# Schema.net
KiCad netlist of a schematic drawn in Altium Designer
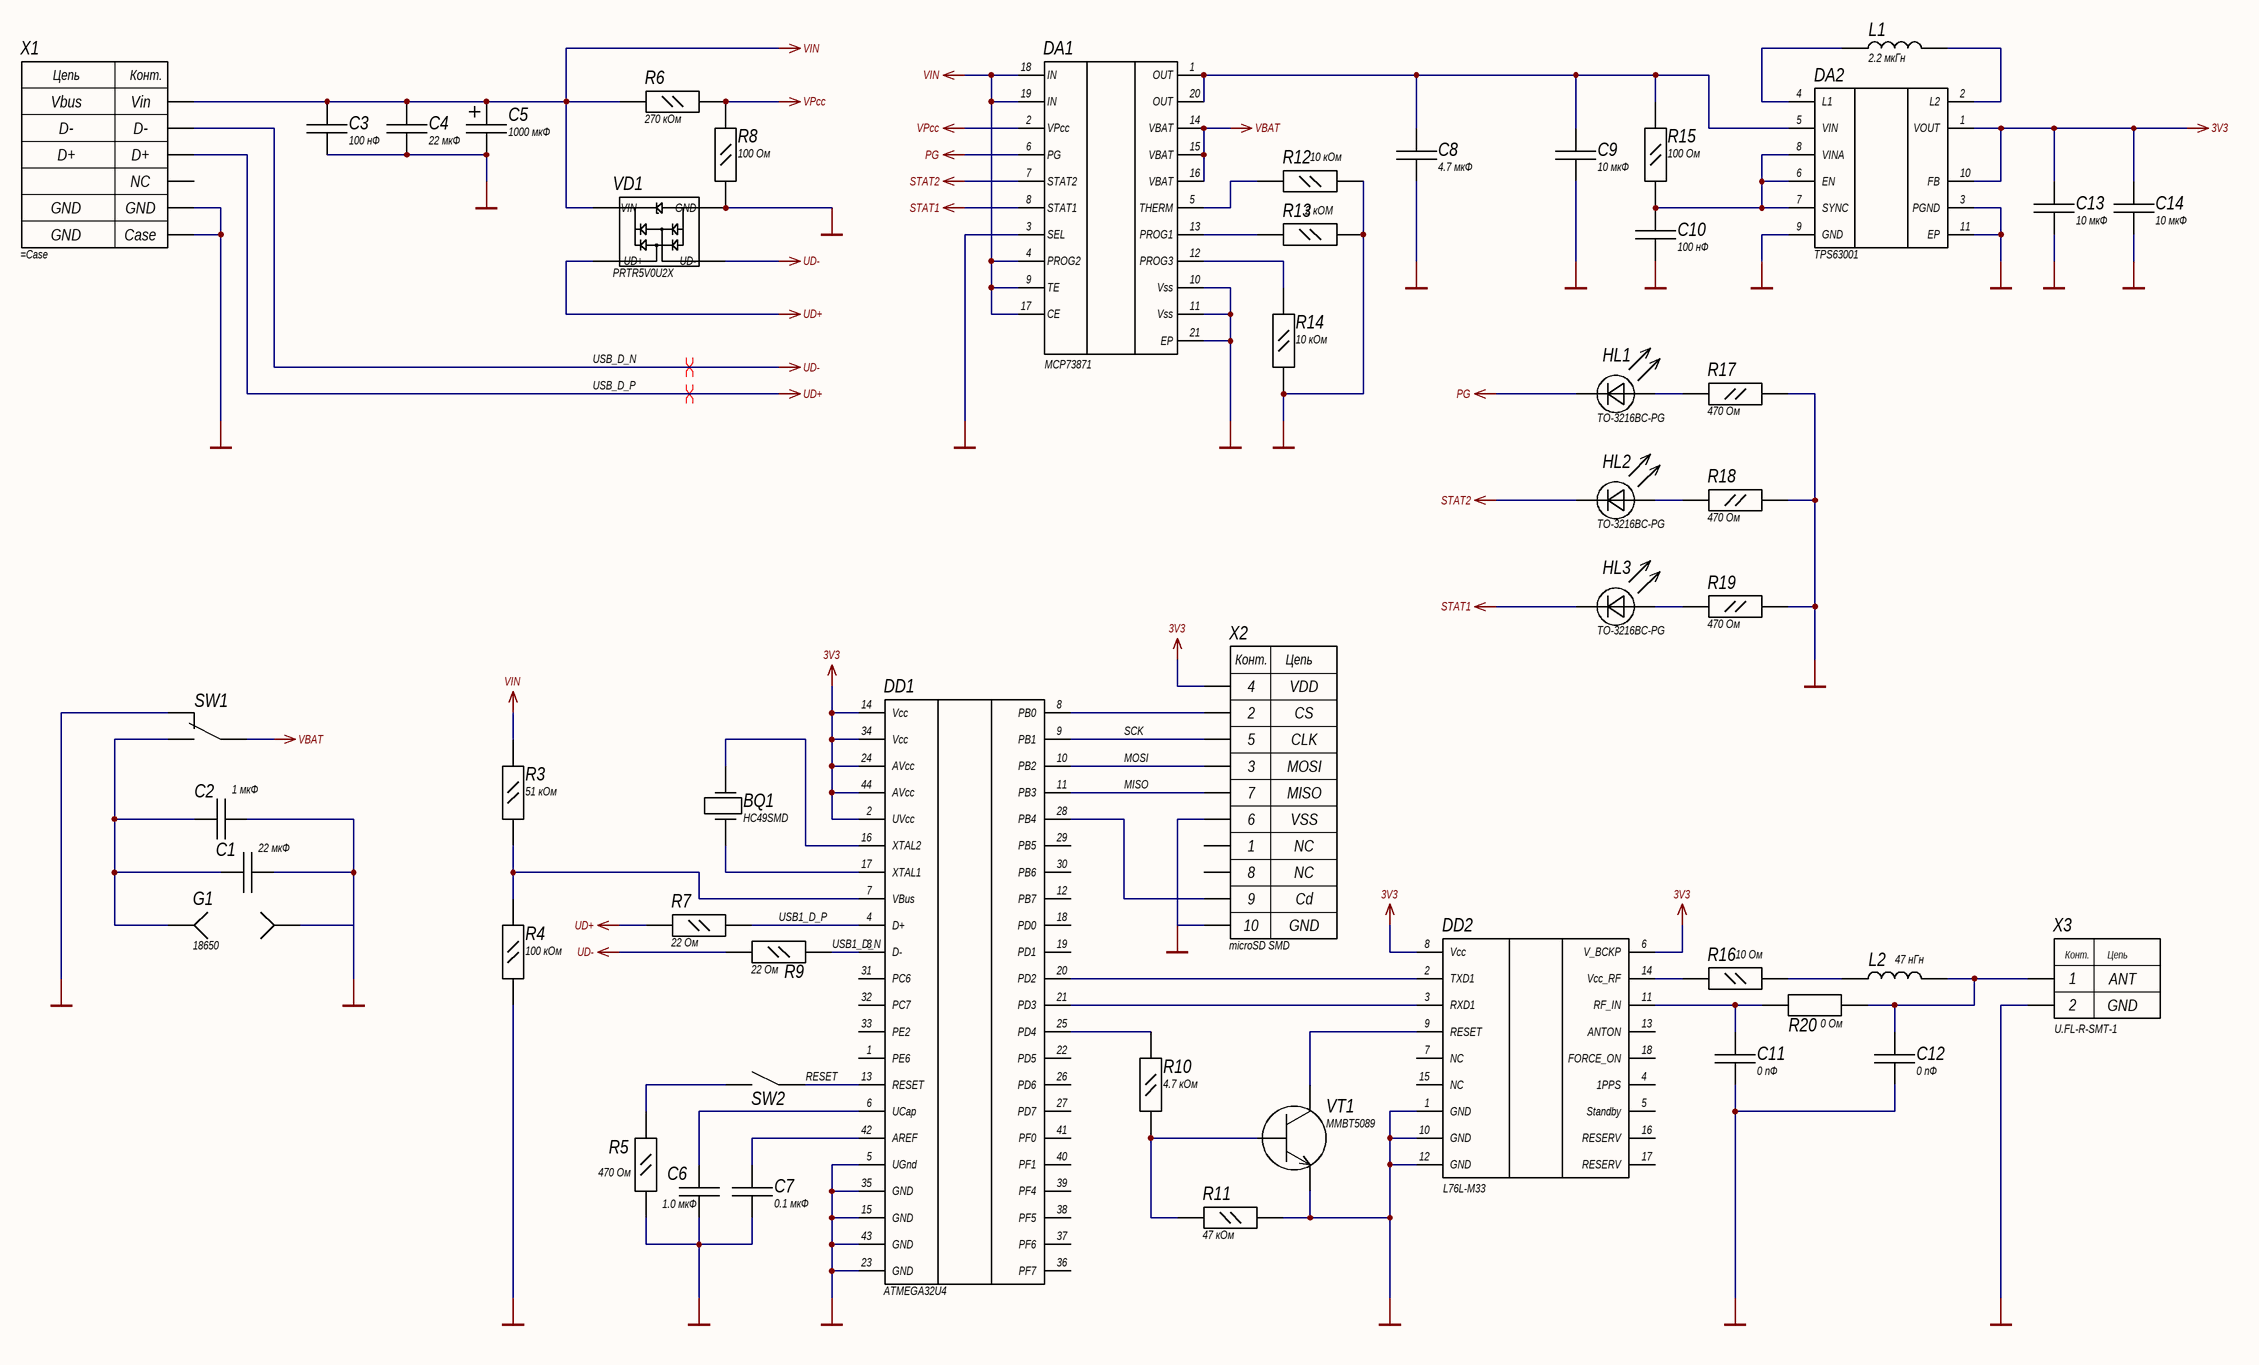
[diagram p0: Schema.SchDoc]

(export (version "E")
  (design (tool "Eeschema 10.0.6"))
  (components
    (comp (ref "BQ1")
      (value "HC49SMD")
      (footprint "HC49SMD")
      (description "Кварцевый резонатор , монтаж SMD")
      (fields (field (name "TOLERANCE") "20 ppm"))
      (libsource (lib "MarginLib") (part "Quartz"))
    )
    (comp (ref "C1")
      (value "22 мкФ")
      (footprint "CC0805")
      (description "безвыводные керамические неполярные конденсаторы общего применения")
      (fields (field (name "PART NUMBER") "GRM21BR61E226ME44L") (field (name "TOLERANCE") "20%"))
      (libsource (lib "MarginLib") (part "Capasitor"))
    )
    (comp (ref "C2")
      (value "1 мкФ")
      (footprint "CC0805")
      (description "безвыводные керамические неполярные конденсаторы общего применения")
      (fields (field (name "PART NUMBER") "GRM21BR71H105KA12L") (field (name "TOLERANCE") "10%"))
      (libsource (lib "MarginLib") (part "Capasitor"))
    )
    (comp (ref "C3")
      (value "100 нФ")
      (footprint "CC0805")
      (description "безвыводные керамические неполярные конденсаторы общего применения")
      (fields (field (name "PART NUMBER") "CL21F104ZBCNNNC") (field (name "TOLERANCE") "10%"))
      (libsource (lib "MarginLib") (part "Capasitor"))
    )
    (comp (ref "C4")
      (value "22 мкФ")
      (footprint "CC0805")
      (description "безвыводные керамические неполярные конденсаторы общего применения")
      (fields (field (name "PART NUMBER") "GRM21BR61E226ME44L") (field (name "TOLERANCE") "20%"))
      (libsource (lib "MarginLib") (part "Capasitor"))
    )
    (comp (ref "C5")
      (value "1000 мкФ")
      (footprint "SMD_CAP_10x10.5")
      (description "Алюминиевые электролитические конденсаторы")
      (fields (field (name "PART NUMBER") "JCK1A102M100105") (field (name "TOLERANCE") "20%"))
      (libsource (lib "MarginLib") (part "Capasitor_pol"))
    )
    (comp (ref "C6")
      (value "1.0 мкФ")
      (footprint "CC0805")
      (fields
        (field (name "PART NUMBER") "GRM21BR71C105KA01K")
        (field (name "TOLERANCE") "10%")
        (field (name "VOLTAGE") "50В")
      )
      (libsource (lib "MarginLib") (part "Capasitor"))
    )
    (comp (ref "C7")
      (value "0.1 мкФ")
      (footprint "CC0805")
      (fields
        (field (name "PART NUMBER") "GRM21BR71H104K")
        (field (name "TOLERANCE") "10%")
        (field (name "VOLTAGE") "50В")
      )
      (libsource (lib "MarginLib") (part "Capasitor"))
    )
    (comp (ref "C8")
      (value "4.7 мкФ")
      (footprint "CC0805")
      (description "безвыводные керамические неполярные конденсаторы общего применения")
      (fields (field (name "PART NUMBER") "GRM21BR61A475KA73L") (field (name "TOLERANCE") "10%"))
      (libsource (lib "MarginLib") (part "Capasitor"))
    )
    (comp (ref "C9")
      (value "10 мкФ")
      (footprint "CC0805")
      (description "безвыводные керамические неполярные конденсаторы общего применения")
      (fields (field (name "PART NUMBER") "GRM21BR61H106KE43L") (field (name "TOLERANCE") "10%"))
      (libsource (lib "MarginLib") (part "Capasitor"))
    )
    (comp (ref "C10")
      (value "100 нФ")
      (footprint "CC0805")
      (description "безвыводные керамические неполярные конденсаторы общего применения")
      (fields (field (name "PART NUMBER") "CL21F104ZBCNNNC") (field (name "TOLERANCE") "10%"))
      (libsource (lib "MarginLib") (part "Capasitor"))
    )
    (comp (ref "C11")
      (value "0 пФ")
      (footprint "CC0805_0")
      (description "Перемычка")
      (fields (field (name "PART NUMBER") "0F"))
      (libsource (lib "MarginLib") (part "Capasitor"))
    )
    (comp (ref "C12")
      (value "0 пФ")
      (footprint "CC0805_0")
      (description "Перемычка")
      (fields (field (name "PART NUMBER") "0F"))
      (libsource (lib "MarginLib") (part "Capasitor"))
    )
    (comp (ref "C13")
      (value "10 мкФ")
      (footprint "CC0805")
      (description "безвыводные керамические неполярные конденсаторы общего применения")
      (fields (field (name "PART NUMBER") "GRM21BR61H106KE43L") (field (name "TOLERANCE") "10%"))
      (libsource (lib "MarginLib") (part "Capasitor"))
    )
    (comp (ref "C14")
      (value "10 мкФ")
      (footprint "CC0805")
      (description "безвыводные керамические неполярные конденсаторы общего применения")
      (fields (field (name "PART NUMBER") "GRM21BR61H106KE43L") (field (name "TOLERANCE") "10%"))
      (libsource (lib "MarginLib") (part "Capasitor"))
    )
    (comp (ref "DA1")
      (value "MCP73871")
      (footprint "QFN-20")
      (fields (field (name "PART NUMBER") "MCP73871-2CCI/ML"))
      (libsource (lib "MarginLib") (part "MCP73871"))
    )
    (comp (ref "DA2")
      (value "TPS63001")
      (footprint "VSON10")
      (description "Преобразователь постоянного тока понижающий-повышающий синхронный 3.3В")
      (fields (field (name "PART NUMBER") "TPS63001DRCR"))
      (libsource (lib "MarginLib") (part "TPS63001"))
    )
    (comp (ref "DD1")
      (value "ATMEGA32U4")
      (footprint "TQFP-44")
      (fields (field (name "PART NUMBER") "ATMEGA32U4-AU"))
      (libsource (lib "MarginLib") (part "ATMEGA32U4"))
    )
    (comp (ref "DD2")
      (value "L76L-M33")
      (footprint "L76-M33")
      (description "GPS/GLONAS модуль")
      (libsource (lib "MarginLib") (part "L76L-M33"))
    )
    (comp (ref "G1")
      (value "18650")
      (footprint "KLS5-18650")
      (description "Держатели батарей, клипсы, контакты")
      (fields (field (name "PART NUMBER") "KLS5-18650-006"))
      (libsource (lib "MarginLib") (part "18650-Battery"))
    )
    (comp (ref "HL1")
      (value "TO-3216BC-PG")
      (footprint "LED_1206_Green")
      (fields (field (name "PART NUMBER") "9203T013"))
      (libsource (lib "MarginLib") (part "LED"))
    )
    (comp (ref "HL2")
      (value "TO-3216BC-PG")
      (footprint "LED_1206_Green")
      (fields (field (name "PART NUMBER") "9203T013"))
      (libsource (lib "MarginLib") (part "LED"))
    )
    (comp (ref "HL3")
      (value "TO-3216BC-PG")
      (footprint "LED_1206_Green")
      (fields (field (name "PART NUMBER") "9203T013"))
      (libsource (lib "MarginLib") (part "LED"))
    )
    (comp (ref "L1")
      (value "2.2 мкГн")
      (footprint "SMD-CDSP43")
      (description "=ValueType+' '+EffectiveValue+' ±'+Tolerance")
      (fields (field (name "PART NUMBER") "CDSP43-2R2M") (field (name "TOLERANCE") "20%"))
      (libsource (lib "MarginLib") (part "Inductor"))
    )
    (comp (ref "L2")
      (value "47 нГн")
      (footprint "0402")
      (description "High quality coil inductors designed for VHF and UHF applications")
      (fields (field (name "PART NUMBER") "LQW15AN47NJ00D") (field (name "TOLERANCE") "5%"))
      (libsource (lib "MarginLib") (part "Inductor"))
    )
    (comp (ref "R3")
      (value "51 кОм")
      (footprint "RC0805")
      (fields
        (field (name "PART NUMBER") "RC0805FR-0751KL")
        (field (name "POWER") "0.125Вт")
        (field (name "TOLERANCE") "1%")
      )
      (libsource (lib "MarginLib") (part "Res_0.125W"))
    )
    (comp (ref "R4")
      (value "100 кОм")
      (footprint "RC0805")
      (fields
        (field (name "PART NUMBER") "RC0805FR-07100KL")
        (field (name "POWER") "0.125Вт")
        (field (name "TOLERANCE") "1%")
      )
      (libsource (lib "MarginLib") (part "Res_0.125W"))
    )
    (comp (ref "R5")
      (value "470 Ом")
      (footprint "RC0805")
      (fields
        (field (name "PART NUMBER") "RC0805FR-07470RL")
        (field (name "POWER") "0.125Вт")
        (field (name "TOLERANCE") "1%")
      )
      (libsource (lib "MarginLib") (part "Res_0.125W"))
    )
    (comp (ref "R6")
      (value "270 кОм")
      (footprint "RC0805")
      (fields
        (field (name "PART NUMBER") "RC0805FR-07270KL")
        (field (name "POWER") "0.125Вт")
        (field (name "TOLERANCE") "1%")
      )
      (libsource (lib "MarginLib") (part "Res_0.125W"))
    )
    (comp (ref "R7")
      (value "22 Ом")
      (footprint "RC0805")
      (fields
        (field (name "PART NUMBER") "RC0805FR-0722RL")
        (field (name "POWER") "0.125Вт")
        (field (name "TOLERANCE") "1%")
      )
      (libsource (lib "MarginLib") (part "Res_0.125W"))
    )
    (comp (ref "R8")
      (value "100 Ом")
      (footprint "RC0805")
      (fields
        (field (name "PART NUMBER") "RC0805FR-07100RL")
        (field (name "POWER") "0.125Вт")
        (field (name "TOLERANCE") "1%")
      )
      (libsource (lib "MarginLib") (part "Res_0.125W"))
    )
    (comp (ref "R9")
      (value "22 Ом")
      (footprint "RC0805")
      (fields
        (field (name "PART NUMBER") "RC0805FR-0722RL")
        (field (name "POWER") "0.125Вт")
        (field (name "TOLERANCE") "1%")
      )
      (libsource (lib "MarginLib") (part "Res_0.125W"))
    )
    (comp (ref "R10")
      (value "4.7 кОм")
      (footprint "RC0805")
      (fields
        (field (name "PART NUMBER") "RC0805FR-074K7L")
        (field (name "POWER") "0.125Вт")
        (field (name "TOLERANCE") "1%")
      )
      (libsource (lib "MarginLib") (part "Res_0.125W"))
    )
    (comp (ref "R11")
      (value "47 кОм")
      (footprint "RC0805")
      (fields
        (field (name "PART NUMBER") "RC0805FR-0747KL")
        (field (name "POWER") "0.125Вт")
        (field (name "TOLERANCE") "1%")
      )
      (libsource (lib "MarginLib") (part "Res_0.125W"))
    )
    (comp (ref "R12")
      (value "10 кОм")
      (footprint "RC0805")
      (fields
        (field (name "PART NUMBER") "RC0805FR-0710KL")
        (field (name "POWER") "0.125Вт")
        (field (name "TOLERANCE") "1%")
      )
      (libsource (lib "MarginLib") (part "Res_0.125W"))
    )
    (comp (ref "R13")
      (value "2 кОМ")
      (footprint "RC0805")
      (fields
        (field (name "PART NUMBER") "RC0805FR-072KL")
        (field (name "POWER") "0.125Вт")
        (field (name "TOLERANCE") "1%")
      )
      (libsource (lib "MarginLib") (part "Res_0.125W"))
    )
    (comp (ref "R14")
      (value "10 кОм")
      (footprint "RC0805")
      (fields
        (field (name "PART NUMBER") "RC0805FR-0710KL")
        (field (name "POWER") "0.125Вт")
        (field (name "TOLERANCE") "1%")
      )
      (libsource (lib "MarginLib") (part "Res_0.125W"))
    )
    (comp (ref "R15")
      (value "100 Ом")
      (footprint "RC0805")
      (fields
        (field (name "PART NUMBER") "RC0805FR-07100RL")
        (field (name "POWER") "0.125Вт")
        (field (name "TOLERANCE") "1%")
      )
      (libsource (lib "MarginLib") (part "Res_0.125W"))
    )
    (comp (ref "R16")
      (value "10 Ом")
      (footprint "RC0805")
      (fields
        (field (name "PART NUMBER") "RC0805FR-0710RL")
        (field (name "POWER") "0.125Вт")
        (field (name "TOLERANCE") "1%")
      )
      (libsource (lib "MarginLib") (part "Res_0.125W"))
    )
    (comp (ref "R17")
      (value "470 Ом")
      (footprint "RC0805")
      (fields
        (field (name "PART NUMBER") "RC0805FR-07470RL")
        (field (name "POWER") "0.125Вт")
        (field (name "TOLERANCE") "1%")
      )
      (libsource (lib "MarginLib") (part "Res_0.125W"))
    )
    (comp (ref "R18")
      (value "470 Ом")
      (footprint "RC0805")
      (fields
        (field (name "PART NUMBER") "RC0805FR-07470RL")
        (field (name "POWER") "0.125Вт")
        (field (name "TOLERANCE") "1%")
      )
      (libsource (lib "MarginLib") (part "Res_0.125W"))
    )
    (comp (ref "R19")
      (value "470 Ом")
      (footprint "RC0805")
      (fields
        (field (name "PART NUMBER") "RC0805FR-07470RL")
        (field (name "POWER") "0.125Вт")
        (field (name "TOLERANCE") "1%")
      )
      (libsource (lib "MarginLib") (part "Res_0.125W"))
    )
    (comp (ref "R20")
      (value "0 Ом")
      (footprint "RC0805_0")
      (description "0 Ом перемычка")
      (fields (field (name "PART NUMBER") "0 Ohm"))
      (libsource (lib "MarginLib") (part "Res_0"))
    )
    (comp (ref "SW1")
      (value "SPDT_Switch")
      (footprint "SPDT-Horizontal")
      (description "=ValueType+' '+Case")
      (fields (field (name "PART NUMBER") "500SSP1S1M6QEA"))
      (libsource (lib "MarginLib") (part "SPDT_Switch"))
    )
    (comp (ref "SW2")
      (value "SW")
      (footprint "6x6_SMD")
      (description "Кнопка тактильная 6х6мм h=5мм усилие нажатия 180гр SMD монтаж россыпь")
      (fields (field (name "PART NUMBER") "L-KLS7-TS6604-5.0-180-B"))
      (libsource (lib "MarginLib") (part "SPST_Switch"))
    )
    (comp (ref "VD1")
      (value "PRTR5V0U2X")
      (footprint "SOT143")
      (libsource (lib "MarginLib") (part "PRTR5V0U2X"))
    )
    (comp (ref "VT1")
      (value "MMBT5089")
      (footprint "SOT23")
      (description "Аналог КТ3102Е")
      (libsource (lib "MarginLib") (part "NPN_Transistor"))
    )
    (comp (ref "X1")
      (value "~")
      (footprint "USB-B-micro")
      (description "USB - micro B USB 2.0 Receptacle Connector 5 Position Surface Mount, Right Angle; Through Hole")
      (fields (field (name "PART NUMBER") "10118194-0001LF"))
      (libsource (lib "MarginLib") (part "USB-B-micro"))
    )
    (comp (ref "X2")
      (value "microSD SMD")
      (footprint "microSD-SMD")
      (description "Держатель micro SD карты SMD 8 pin")
      (fields (field (name "PART NUMBER") "112J-TDAR-R01"))
      (libsource (lib "MarginLib") (part "microSD"))
    )
    (comp (ref "X3")
      (value "U.FL-R-SMT-1")
      (footprint "U.FL-R-SMT-1")
      (description "Разъем UFL 50 Ом на плату SMT")
      (fields (field (name "PART NUMBER") "U.FL-R-SMT-1[80]"))
      (libsource (lib "MarginLib") (part "U.FL"))
    )
  )
  (nets
    (net (code "1") (name "/MISO") (class "Default")
      (node (ref "DD1") (pin "11") (pinfunction "PB3_11") (pintype "passive"))
      (node (ref "X2") (pin "7") (pinfunction "7_7") (pintype "passive"))
    )
    (net (code "2") (name "/MOSI") (class "Default")
      (node (ref "DD1") (pin "10") (pinfunction "PB2_10") (pintype "passive"))
      (node (ref "X2") (pin "3") (pinfunction "3_3") (pintype "passive"))
    )
    (net (code "3") (name "/RESET") (class "Default")
      (node (ref "DD1") (pin "13") (pinfunction "RESET_13") (pintype "passive"))
      (node (ref "SW2") (pin "2") (pinfunction "2_2") (pintype "passive"))
    )
    (net (code "4") (name "/SCK") (class "Default")
      (node (ref "DD1") (pin "9") (pinfunction "PB1_9") (pintype "passive"))
      (node (ref "X2") (pin "5") (pinfunction "5_5") (pintype "passive"))
    )
    (net (code "5") (name "/USB1_D_N") (class "Default")
      (node (ref "DD1") (pin "3") (pinfunction "D-_3") (pintype "passive"))
      (node (ref "R9") (pin "1") (pinfunction "1_1") (pintype "passive"))
    )
    (net (code "6") (name "/USB1_D_P") (class "Default")
      (node (ref "DD1") (pin "4") (pinfunction "D+_4") (pintype "passive"))
      (node (ref "R7") (pin "1") (pinfunction "1_1") (pintype "passive"))
    )
    (net (code "7") (name "3V3") (class "Default")
      (node (ref "C13") (pin "1") (pintype "passive"))
      (node (ref "C14") (pin "1") (pintype "passive"))
      (node (ref "DA2") (pin "1") (pinfunction "VOUT_1") (pintype "passive"))
      (node (ref "DA2") (pin "10") (pinfunction "FB_10") (pintype "passive"))
      (node (ref "DD1") (pin "14") (pinfunction "Vcc_14") (pintype "passive"))
      (node (ref "DD1") (pin "2") (pinfunction "UVcc_2") (pintype "passive"))
      (node (ref "DD1") (pin "24") (pinfunction "AVcc_24") (pintype "passive"))
      (node (ref "DD1") (pin "34") (pinfunction "Vcc_34") (pintype "passive"))
      (node (ref "DD1") (pin "44") (pinfunction "AVcc_44") (pintype "passive"))
      (node (ref "DD2") (pin "6") (pinfunction "V_BCKP_6") (pintype "passive"))
      (node (ref "DD2") (pin "8") (pinfunction "Vcc_8") (pintype "passive"))
      (node (ref "X2") (pin "4") (pinfunction "4_4") (pintype "passive"))
    )
    (net (code "8") (name "GND") (class "Default")
      (node (ref "C1") (pin "2") (pintype "passive"))
      (node (ref "C10") (pin "2") (pintype "passive"))
      (node (ref "C11") (pin "2") (pintype "passive"))
      (node (ref "C12") (pin "2") (pintype "passive"))
      (node (ref "C13") (pin "2") (pintype "passive"))
      (node (ref "C14") (pin "2") (pintype "passive"))
      (node (ref "C2") (pin "2") (pintype "passive"))
      (node (ref "C3") (pin "2") (pintype "passive"))
      (node (ref "C4") (pin "2") (pintype "passive"))
      (node (ref "C5") (pin "1") (pinfunction "1_1") (pintype "passive"))
      (node (ref "C6") (pin "2") (pintype "passive"))
      (node (ref "C7") (pin "2") (pintype "passive"))
      (node (ref "C8") (pin "2") (pintype "passive"))
      (node (ref "C9") (pin "2") (pintype "passive"))
      (node (ref "DA1") (pin "10") (pinfunction "Vss_10") (pintype "passive"))
      (node (ref "DA1") (pin "11") (pinfunction "Vss_11") (pintype "passive"))
      (node (ref "DA1") (pin "21") (pinfunction "EP_21") (pintype "passive"))
      (node (ref "DA1") (pin "3") (pinfunction "SEL_3") (pintype "passive"))
      (node (ref "DA2") (pin "11") (pinfunction "EP_11") (pintype "passive"))
      (node (ref "DA2") (pin "3") (pinfunction "PGND_3") (pintype "passive"))
      (node (ref "DA2") (pin "9") (pinfunction "GND_9") (pintype "passive"))
      (node (ref "DD1") (pin "15") (pinfunction "GND_15") (pintype "passive"))
      (node (ref "DD1") (pin "23") (pinfunction "GND_23") (pintype "passive"))
      (node (ref "DD1") (pin "35") (pinfunction "GND_35") (pintype "passive"))
      (node (ref "DD1") (pin "43") (pinfunction "GND_43") (pintype "passive"))
      (node (ref "DD1") (pin "5") (pinfunction "UGnd_5") (pintype "passive"))
      (node (ref "DD2") (pin "1") (pinfunction "GND_1") (pintype "passive"))
      (node (ref "DD2") (pin "10") (pinfunction "GND_10") (pintype "passive"))
      (node (ref "DD2") (pin "12") (pinfunction "GND_12") (pintype "passive"))
      (node (ref "G1") (pin "Minus") (pinfunction "Minus_Minus") (pintype "passive"))
      (node (ref "R11") (pin "1") (pinfunction "1_1") (pintype "passive"))
      (node (ref "R12") (pin "1") (pinfunction "1_1") (pintype "passive"))
      (node (ref "R13") (pin "1") (pinfunction "1_1") (pintype "passive"))
      (node (ref "R14") (pin "1") (pinfunction "1_1") (pintype "passive"))
      (node (ref "R17") (pin "2") (pinfunction "2_2") (pintype "passive"))
      (node (ref "R18") (pin "2") (pinfunction "2_2") (pintype "passive"))
      (node (ref "R19") (pin "2") (pinfunction "2_2") (pintype "passive"))
      (node (ref "R4") (pin "2") (pinfunction "2_2") (pintype "passive"))
      (node (ref "R5") (pin "1") (pinfunction "1_1") (pintype "passive"))
      (node (ref "R8") (pin "1") (pinfunction "1_1") (pintype "passive"))
      (node (ref "SW1") (pin "NC") (pinfunction "NC_NC") (pintype "passive"))
      (node (ref "VD1") (pin "1") (pinfunction "GND_1") (pintype "passive"))
      (node (ref "VT1") (pin "2") (pinfunction "E_2") (pintype "passive"))
      (node (ref "X1") (pin "5") (pinfunction "Vin_5") (pintype "passive"))
      (node (ref "X1") (pin "6") (pinfunction "6_6") (pintype "passive"))
      (node (ref "X2") (pin "6") (pinfunction "6_6") (pintype "passive"))
      (node (ref "X2") (pin "GND") (pinfunction "10_GND") (pintype "passive"))
      (node (ref "X3") (pin "2") (pinfunction "2_2") (pintype "passive"))
    )
    (net (code "9") (name "Net-(C1-Pad1)") (class "Default")
      (node (ref "C1") (pin "1") (pintype "passive"))
      (node (ref "C2") (pin "1") (pintype "passive"))
      (node (ref "G1") (pin "Plus") (pinfunction "Plus_Plus") (pintype "passive"))
      (node (ref "SW1") (pin "NO") (pinfunction "NO_NO") (pintype "passive"))
    )
    (net (code "10") (name "Net-(C12-Pad1)") (class "Default")
      (node (ref "C12") (pin "1") (pintype "passive"))
      (node (ref "L2") (pin "2") (pinfunction "2_2") (pintype "passive"))
      (node (ref "R20") (pin "1") (pinfunction "1_1") (pintype "passive"))
      (node (ref "X3") (pin "1") (pinfunction "1_1") (pintype "passive"))
    )
    (net (code "11") (name "Net-(DA1-PROG1)") (class "Default")
      (node (ref "DA1") (pin "13") (pinfunction "PROG1_13") (pintype "passive"))
      (node (ref "R13") (pin "2") (pinfunction "2_2") (pintype "passive"))
    )
    (net (code "12") (name "Net-(DA1-PROG3)") (class "Default")
      (node (ref "DA1") (pin "12") (pinfunction "PROG3_12") (pintype "passive"))
      (node (ref "R14") (pin "2") (pinfunction "2_2") (pintype "passive"))
    )
    (net (code "13") (name "Net-(DA1-THERM)") (class "Default")
      (node (ref "DA1") (pin "5") (pinfunction "THERM_5") (pintype "passive"))
      (node (ref "R12") (pin "2") (pinfunction "2_2") (pintype "passive"))
    )
    (net (code "14") (name "Net-(DA2-EN)") (class "Default")
      (node (ref "C10") (pin "1") (pintype "passive"))
      (node (ref "DA2") (pin "6") (pinfunction "EN_6") (pintype "passive"))
      (node (ref "DA2") (pin "7") (pinfunction "SYNC_7") (pintype "passive"))
      (node (ref "DA2") (pin "8") (pinfunction "VINA_8") (pintype "passive"))
      (node (ref "R15") (pin "2") (pinfunction "2_2") (pintype "passive"))
    )
    (net (code "15") (name "Net-(DA2-L1)") (class "Default")
      (node (ref "DA2") (pin "4") (pinfunction "L1_4") (pintype "passive"))
      (node (ref "L1") (pin "1") (pinfunction "1_1") (pintype "passive"))
    )
    (net (code "16") (name "Net-(DA2-L2)") (class "Default")
      (node (ref "DA2") (pin "2") (pinfunction "L2_2") (pintype "passive"))
      (node (ref "L1") (pin "2") (pinfunction "2_2") (pintype "passive"))
    )
    (net (code "17") (name "Net-(DA2-VIN)") (class "Default")
      (node (ref "C8") (pin "1") (pintype "passive"))
      (node (ref "C9") (pin "1") (pintype "passive"))
      (node (ref "DA1") (pin "1") (pinfunction "OUT_1") (pintype "passive"))
      (node (ref "DA1") (pin "20") (pinfunction "OUT_20") (pintype "passive"))
      (node (ref "DA2") (pin "5") (pinfunction "VIN_5") (pintype "passive"))
      (node (ref "R15") (pin "1") (pinfunction "1_1") (pintype "passive"))
    )
    (net (code "18") (name "Net-(DD1-AREF)") (class "Default")
      (node (ref "C7") (pin "1") (pintype "passive"))
      (node (ref "DD1") (pin "42") (pinfunction "AREF_42") (pintype "passive"))
    )
    (net (code "19") (name "Net-(DD1-PB0)") (class "Default")
      (node (ref "DD1") (pin "8") (pinfunction "PB0_8") (pintype "passive"))
      (node (ref "X2") (pin "2") (pinfunction "2_2") (pintype "passive"))
    )
    (net (code "20") (name "Net-(DD1-PB4)") (class "Default")
      (node (ref "DD1") (pin "28") (pinfunction "PB4_28") (pintype "passive"))
      (node (ref "X2") (pin "Cd") (pinfunction "9_Cd") (pintype "passive"))
    )
    (net (code "21") (name "Net-(DD1-PD2)") (class "Default")
      (node (ref "DD1") (pin "20") (pinfunction "PD2_20") (pintype "passive"))
      (node (ref "DD2") (pin "2") (pinfunction "TXD1_2") (pintype "passive"))
    )
    (net (code "22") (name "Net-(DD1-PD3)") (class "Default")
      (node (ref "DD1") (pin "21") (pinfunction "PD3_21") (pintype "passive"))
      (node (ref "DD2") (pin "3") (pinfunction "RXD1_3") (pintype "passive"))
    )
    (net (code "23") (name "Net-(DD1-PD4)") (class "Default")
      (node (ref "DD1") (pin "25") (pinfunction "PD4_25") (pintype "passive"))
      (node (ref "R10") (pin "2") (pinfunction "2_2") (pintype "passive"))
    )
    (net (code "24") (name "Net-(DD1-UCap)") (class "Default")
      (node (ref "C6") (pin "1") (pintype "passive"))
      (node (ref "DD1") (pin "6") (pinfunction "UCap_6") (pintype "passive"))
    )
    (net (code "25") (name "Net-(DD1-VBus)") (class "Default")
      (node (ref "DD1") (pin "7") (pinfunction "VBus_7") (pintype "passive"))
      (node (ref "R3") (pin "2") (pinfunction "2_2") (pintype "passive"))
      (node (ref "R4") (pin "1") (pinfunction "1_1") (pintype "passive"))
    )
    (net (code "26") (name "Net-(DD1-XTAL1)") (class "Default")
      (node (ref "BQ1") (pin "1") (pinfunction "1_1") (pintype "passive"))
      (node (ref "DD1") (pin "17") (pinfunction "XTAL1_17") (pintype "passive"))
    )
    (net (code "27") (name "Net-(DD1-XTAL2)") (class "Default")
      (node (ref "BQ1") (pin "2") (pinfunction "2_2") (pintype "passive"))
      (node (ref "DD1") (pin "16") (pinfunction "XTAL2_16") (pintype "passive"))
    )
    (net (code "28") (name "Net-(DD2-RESET)") (class "Default")
      (node (ref "DD2") (pin "9") (pinfunction "RESET_9") (pintype "passive"))
      (node (ref "VT1") (pin "3") (pinfunction "C_3") (pintype "passive"))
    )
    (net (code "29") (name "Net-(DD2-RF_IN)") (class "Default")
      (node (ref "C11") (pin "1") (pintype "passive"))
      (node (ref "DD2") (pin "11") (pinfunction "RF_IN_11") (pintype "passive"))
      (node (ref "R20") (pin "2") (pinfunction "2_2") (pintype "passive"))
    )
    (net (code "30") (name "Net-(DD2-Vcc_RF)") (class "Default")
      (node (ref "DD2") (pin "14") (pinfunction "Vcc_RF_14") (pintype "passive"))
      (node (ref "R16") (pin "2") (pinfunction "2_2") (pintype "passive"))
    )
    (net (code "31") (name "Net-(HL1-PadA)") (class "Default")
      (node (ref "HL1") (pin "A") (pinfunction "A_A") (pintype "passive"))
      (node (ref "R17") (pin "1") (pinfunction "1_1") (pintype "passive"))
    )
    (net (code "32") (name "Net-(HL2-PadA)") (class "Default")
      (node (ref "HL2") (pin "A") (pinfunction "A_A") (pintype "passive"))
      (node (ref "R18") (pin "1") (pinfunction "1_1") (pintype "passive"))
    )
    (net (code "33") (name "Net-(HL3-PadA)") (class "Default")
      (node (ref "HL3") (pin "A") (pinfunction "A_A") (pintype "passive"))
      (node (ref "R19") (pin "1") (pinfunction "1_1") (pintype "passive"))
    )
    (net (code "34") (name "Net-(L2-Pad1)") (class "Default")
      (node (ref "L2") (pin "1") (pinfunction "1_1") (pintype "passive"))
      (node (ref "R16") (pin "1") (pinfunction "1_1") (pintype "passive"))
    )
    (net (code "35") (name "Net-(R5-Pad2)") (class "Default")
      (node (ref "R5") (pin "2") (pinfunction "2_2") (pintype "passive"))
      (node (ref "SW2") (pin "1") (pinfunction "1_1") (pintype "passive"))
    )
    (net (code "36") (name "Net-(VT1-B)") (class "Default")
      (node (ref "R10") (pin "1") (pinfunction "1_1") (pintype "passive"))
      (node (ref "R11") (pin "2") (pinfunction "2_2") (pintype "passive"))
      (node (ref "VT1") (pin "1") (pinfunction "B_1") (pintype "passive"))
    )
    (net (code "37") (name "PG") (class "Default")
      (node (ref "DA1") (pin "6") (pinfunction "PG_6") (pintype "passive"))
      (node (ref "HL1") (pin "K") (pinfunction "K_K") (pintype "passive"))
    )
    (net (code "38") (name "STAT1") (class "Default")
      (node (ref "DA1") (pin "8") (pinfunction "STAT1_8") (pintype "passive"))
      (node (ref "HL3") (pin "K") (pinfunction "K_K") (pintype "passive"))
    )
    (net (code "39") (name "STAT2") (class "Default")
      (node (ref "DA1") (pin "7") (pinfunction "STAT2_7") (pintype "passive"))
      (node (ref "HL2") (pin "K") (pinfunction "K_K") (pintype "passive"))
    )
    (net (code "40") (name "UD+") (class "Default")
      (node (ref "R7") (pin "2") (pinfunction "2_2") (pintype "passive"))
      (node (ref "VD1") (pin "3") (pinfunction "UD+_3") (pintype "passive"))
      (node (ref "X1") (pin "3") (pinfunction "Vin_3") (pintype "passive"))
    )
    (net (code "41") (name "UD-") (class "Default")
      (node (ref "R9") (pin "2") (pinfunction "2_2") (pintype "passive"))
      (node (ref "VD1") (pin "2") (pinfunction "UD-_2") (pintype "passive"))
      (node (ref "X1") (pin "2") (pinfunction "Vin_2") (pintype "passive"))
    )
    (net (code "42") (name "VBAT") (class "Default")
      (node (ref "DA1") (pin "14") (pinfunction "VBAT_14") (pintype "passive"))
      (node (ref "DA1") (pin "15") (pinfunction "VBAT_15") (pintype "passive"))
      (node (ref "DA1") (pin "16") (pinfunction "VBAT_16") (pintype "passive"))
      (node (ref "SW1") (pin "COM") (pinfunction "COM_COM") (pintype "passive"))
    )
    (net (code "43") (name "VIN") (class "Default")
      (node (ref "C3") (pin "1") (pintype "passive"))
      (node (ref "C4") (pin "1") (pintype "passive"))
      (node (ref "C5") (pin "2") (pinfunction "2_2") (pintype "passive"))
      (node (ref "DA1") (pin "17") (pinfunction "CE_17") (pintype "passive"))
      (node (ref "DA1") (pin "18") (pinfunction "IN_18") (pintype "passive"))
      (node (ref "DA1") (pin "19") (pinfunction "IN_19") (pintype "passive"))
      (node (ref "DA1") (pin "4") (pinfunction "PROG2_4") (pintype "passive"))
      (node (ref "DA1") (pin "9") (pinfunction "TE_9") (pintype "passive"))
      (node (ref "R3") (pin "1") (pinfunction "1_1") (pintype "passive"))
      (node (ref "R6") (pin "2") (pinfunction "2_2") (pintype "passive"))
      (node (ref "VD1") (pin "4") (pinfunction "VIN_4") (pintype "passive"))
      (node (ref "X1") (pin "1") (pinfunction "1_1") (pintype "passive"))
    )
    (net (code "44") (name "VPcc") (class "Default")
      (node (ref "DA1") (pin "2") (pinfunction "VPcc_2") (pintype "passive"))
      (node (ref "R6") (pin "1") (pinfunction "1_1") (pintype "passive"))
      (node (ref "R8") (pin "2") (pinfunction "2_2") (pintype "passive"))
    )
    (net (code "45") (name "unconnected-(DD1-PB5-Pad29)") (class "Default")
      (node (ref "DD1") (pin "29") (pinfunction "PB5_29") (pintype "passive"))
    )
    (net (code "46") (name "unconnected-(DD1-PB6-Pad30)") (class "Default")
      (node (ref "DD1") (pin "30") (pinfunction "PB6_30") (pintype "passive"))
    )
    (net (code "47") (name "unconnected-(DD1-PB7-Pad12)") (class "Default")
      (node (ref "DD1") (pin "12") (pinfunction "PB7_12") (pintype "passive"))
    )
    (net (code "48") (name "unconnected-(DD1-PC6-Pad31)") (class "Default")
      (node (ref "DD1") (pin "31") (pinfunction "PC6_31") (pintype "passive"))
    )
    (net (code "49") (name "unconnected-(DD1-PC7-Pad32)") (class "Default")
      (node (ref "DD1") (pin "32") (pinfunction "PC7_32") (pintype "passive"))
    )
    (net (code "50") (name "unconnected-(DD1-PD0-Pad18)") (class "Default")
      (node (ref "DD1") (pin "18") (pinfunction "PD0_18") (pintype "passive"))
    )
    (net (code "51") (name "unconnected-(DD1-PD1-Pad19)") (class "Default")
      (node (ref "DD1") (pin "19") (pinfunction "PD1_19") (pintype "passive"))
    )
    (net (code "52") (name "unconnected-(DD1-PD5-Pad22)") (class "Default")
      (node (ref "DD1") (pin "22") (pinfunction "PD5_22") (pintype "passive"))
    )
    (net (code "53") (name "unconnected-(DD1-PD6-Pad26)") (class "Default")
      (node (ref "DD1") (pin "26") (pinfunction "PD6_26") (pintype "passive"))
    )
    (net (code "54") (name "unconnected-(DD1-PD7-Pad27)") (class "Default")
      (node (ref "DD1") (pin "27") (pinfunction "PD7_27") (pintype "passive"))
    )
    (net (code "55") (name "unconnected-(DD1-PE2-Pad33)") (class "Default")
      (node (ref "DD1") (pin "33") (pinfunction "PE2_33") (pintype "passive"))
    )
    (net (code "56") (name "unconnected-(DD1-PE6-Pad1)") (class "Default")
      (node (ref "DD1") (pin "1") (pinfunction "PE6_1") (pintype "passive"))
    )
    (net (code "57") (name "unconnected-(DD1-PF0-Pad41)") (class "Default")
      (node (ref "DD1") (pin "41") (pinfunction "PF0_41") (pintype "passive"))
    )
    (net (code "58") (name "unconnected-(DD1-PF1-Pad40)") (class "Default")
      (node (ref "DD1") (pin "40") (pinfunction "PF1_40") (pintype "passive"))
    )
    (net (code "59") (name "unconnected-(DD1-PF4-Pad39)") (class "Default")
      (node (ref "DD1") (pin "39") (pinfunction "PF4_39") (pintype "passive"))
    )
    (net (code "60") (name "unconnected-(DD1-PF5-Pad38)") (class "Default")
      (node (ref "DD1") (pin "38") (pinfunction "PF5_38") (pintype "passive"))
    )
    (net (code "61") (name "unconnected-(DD1-PF6-Pad37)") (class "Default")
      (node (ref "DD1") (pin "37") (pinfunction "PF6_37") (pintype "passive"))
    )
    (net (code "62") (name "unconnected-(DD1-PF7-Pad36)") (class "Default")
      (node (ref "DD1") (pin "36") (pinfunction "PF7_36") (pintype "passive"))
    )
    (net (code "63") (name "unconnected-(DD2-1PPS-Pad4)") (class "Default")
      (node (ref "DD2") (pin "4") (pinfunction "1PPS_4") (pintype "passive"))
    )
    (net (code "64") (name "unconnected-(DD2-ANTON-Pad13)") (class "Default")
      (node (ref "DD2") (pin "13") (pinfunction "ANTON_13") (pintype "passive"))
    )
    (net (code "65") (name "unconnected-(DD2-FORCE_ON-Pad18)") (class "Default")
      (node (ref "DD2") (pin "18") (pinfunction "FORCE_ON_18") (pintype "passive"))
    )
    (net (code "66") (name "unconnected-(DD2-NC-Pad7)") (class "Default")
      (node (ref "DD2") (pin "7") (pinfunction "NC_7") (pintype "passive"))
    )
    (net (code "67") (name "unconnected-(DD2-NC-Pad15)") (class "Default")
      (node (ref "DD2") (pin "15") (pinfunction "NC_15") (pintype "passive"))
    )
    (net (code "68") (name "unconnected-(DD2-RESERV-Pad16)") (class "Default")
      (node (ref "DD2") (pin "16") (pinfunction "RESERV_16") (pintype "passive"))
    )
    (net (code "69") (name "unconnected-(DD2-RESERV-Pad17)") (class "Default")
      (node (ref "DD2") (pin "17") (pinfunction "RESERV_17") (pintype "passive"))
    )
    (net (code "70") (name "unconnected-(DD2-Standby-Pad5)") (class "Default")
      (node (ref "DD2") (pin "5") (pinfunction "Standby_5") (pintype "passive"))
    )
    (net (code "71") (name "unconnected-(X1-Vin-Pad4)") (class "Default")
      (node (ref "X1") (pin "4") (pinfunction "Vin_4") (pintype "passive"))
    )
    (net (code "72") (name "unconnected-(X2-Pad1)") (class "Default")
      (node (ref "X2") (pin "1") (pinfunction "1_1") (pintype "passive"))
    )
    (net (code "73") (name "unconnected-(X2-Pad8)") (class "Default")
      (node (ref "X2") (pin "8") (pinfunction "8_8") (pintype "passive"))
    )
  )
)
